# Flash.net
KiCad netlist of a schematic drawn in Altium Designer
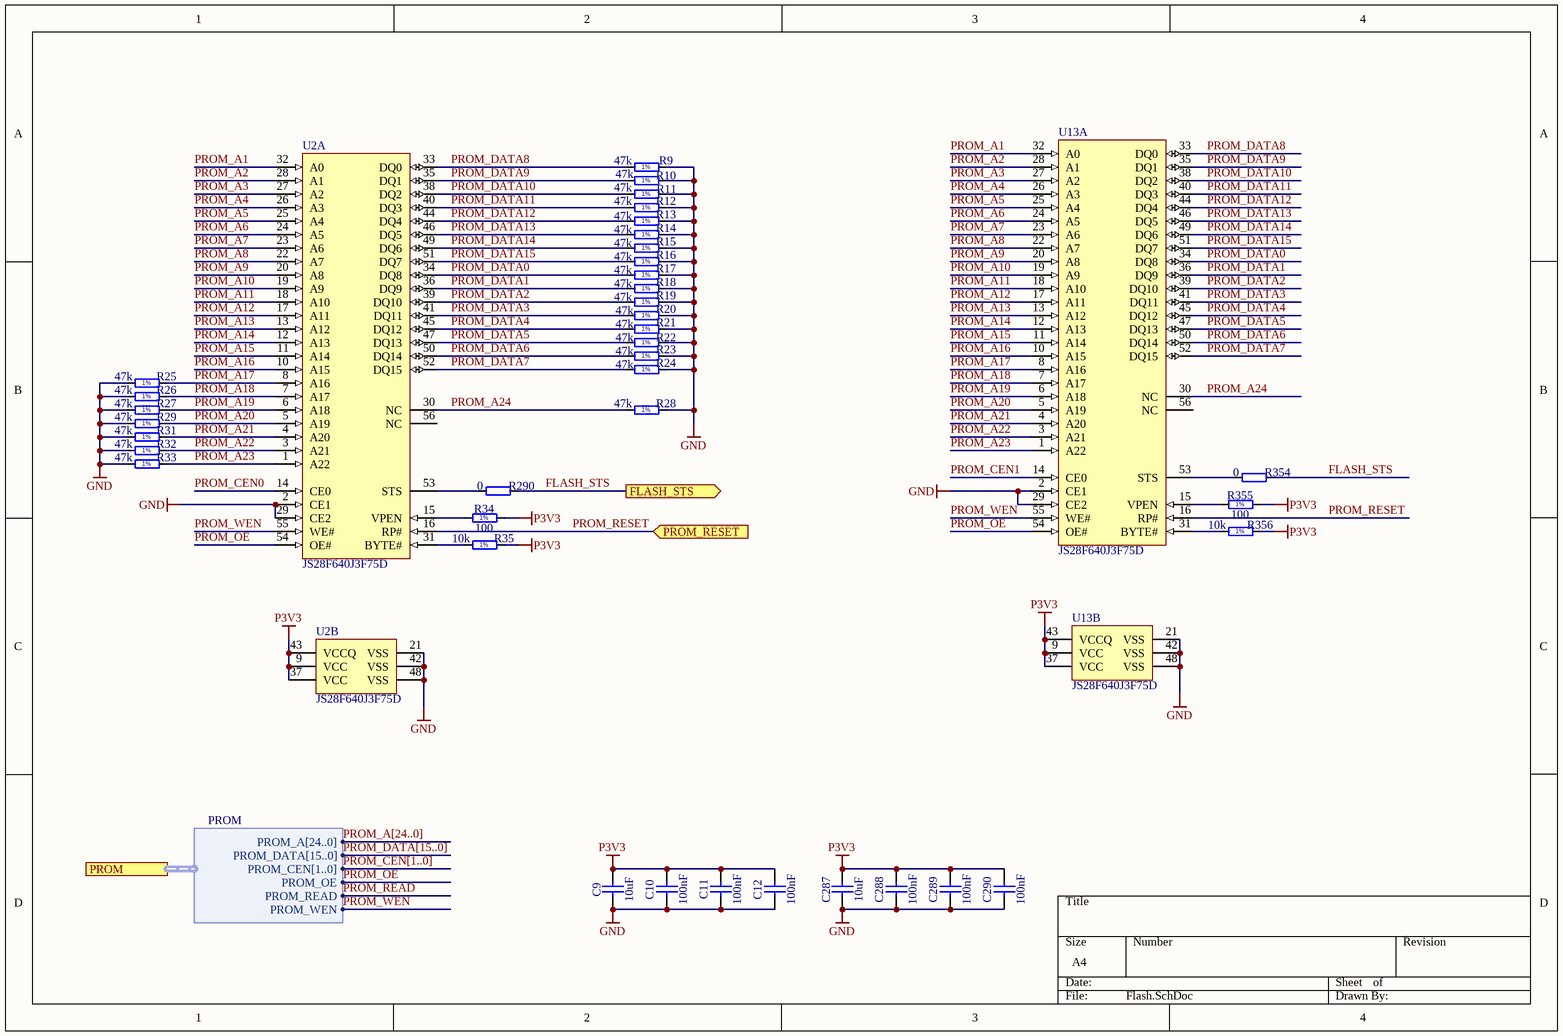
[diagram p0: Flash.SchDoc]

(export (version "E")
  (design (tool "Eeschema 10.0.6"))
  (components
    (comp (ref "C9")
      (value "10uF")
      (footprint "CAPC2012X135N")
      (description "Non-polarised capacitor")
      (fields
        (field (name "PART NUMBER") "CC0805_10UF_16V_10%_X5R")
        (field (name "VOLTAGE") "16V")
        (field (name "AUTHOR") "CERN DEM JLC")
      )
      (libsource (lib "Capacitors") (part "Capacitor - non polarized"))
    )
    (comp (ref "C10")
      (value "100nF")
      (footprint "CAPC0603X33N")
      (description "Non-polarised capacitor")
      (fields
        (field (name "MANUFACTURER") "GENERIC")
        (field (name "PART NUMBER") "CC0201_100NF_6.3V_10%_X5R")
        (field (name "AUTHOR") "CERN DEM JLC")
      )
      (libsource (lib "Capacitors") (part "Capacitor - non polarized"))
    )
    (comp (ref "C11")
      (value "100nF")
      (footprint "CAPC0603X33N")
      (description "Non-polarised capacitor")
      (fields
        (field (name "MANUFACTURER") "GENERIC")
        (field (name "PART NUMBER") "CC0201_100NF_6.3V_10%_X5R")
        (field (name "AUTHOR") "CERN DEM JLC")
      )
      (libsource (lib "Capacitors") (part "Capacitor - non polarized"))
    )
    (comp (ref "C12")
      (value "100nF")
      (footprint "CAPC0603X33N")
      (description "Non-polarised capacitor")
      (fields
        (field (name "MANUFACTURER") "GENERIC")
        (field (name "PART NUMBER") "CC0201_100NF_6.3V_10%_X5R")
        (field (name "AUTHOR") "CERN DEM JLC")
      )
      (libsource (lib "Capacitors") (part "Capacitor - non polarized"))
    )
    (comp (ref "C287")
      (value "10uF")
      (footprint "CAPC2012X135N")
      (description "Non-polarised capacitor")
      (fields
        (field (name "PART NUMBER") "CC0805_10UF_16V_10%_X5R")
        (field (name "VOLTAGE") "16V")
        (field (name "AUTHOR") "CERN DEM JLC")
      )
      (libsource (lib "Capacitors") (part "Capacitor - non polarized"))
    )
    (comp (ref "C288")
      (value "100nF")
      (footprint "CAPC0603X33N")
      (description "Non-polarised capacitor")
      (fields
        (field (name "MANUFACTURER") "GENERIC")
        (field (name "PART NUMBER") "CC0201_100NF_6.3V_10%_X5R")
        (field (name "AUTHOR") "CERN DEM JLC")
      )
      (libsource (lib "Capacitors") (part "Capacitor - non polarized"))
    )
    (comp (ref "C289")
      (value "100nF")
      (footprint "CAPC0603X33N")
      (description "Non-polarised capacitor")
      (fields
        (field (name "MANUFACTURER") "GENERIC")
        (field (name "PART NUMBER") "CC0201_100NF_6.3V_10%_X5R")
        (field (name "AUTHOR") "CERN DEM JLC")
      )
      (libsource (lib "Capacitors") (part "Capacitor - non polarized"))
    )
    (comp (ref "C290")
      (value "100nF")
      (footprint "CAPC0603X33N")
      (description "Non-polarised capacitor")
      (fields
        (field (name "MANUFACTURER") "GENERIC")
        (field (name "PART NUMBER") "CC0201_100NF_6.3V_10%_X5R")
        (field (name "AUTHOR") "CERN DEM JLC")
      )
      (libsource (lib "Capacitors") (part "Capacitor - non polarized"))
    )
    (comp (ref "R9")
      (value "47k")
      (footprint "RESC1005X40N")
      (description "Resistor - 1%")
      (fields
        (field (name "PART NUMBER") "R0402_47K_1%_0.0625W_100PPM")
        (field (name "POWER") "0.0625W")
        (field (name "AUTHOR") "CERN DEM JLC")
      )
      (libsource (lib "Resistors") (part "Resistor - 1%"))
    )
    (comp (ref "R10")
      (value "47k")
      (footprint "RESC1005X40N")
      (description "Resistor - 1%")
      (fields
        (field (name "PART NUMBER") "R0402_47K_1%_0.0625W_100PPM")
        (field (name "POWER") "0.0625W")
        (field (name "AUTHOR") "CERN DEM JLC")
      )
      (libsource (lib "Resistors") (part "Resistor - 1%"))
    )
    (comp (ref "R11")
      (value "47k")
      (footprint "RESC1005X40N")
      (description "Resistor - 1%")
      (fields
        (field (name "PART NUMBER") "R0402_47K_1%_0.0625W_100PPM")
        (field (name "POWER") "0.0625W")
        (field (name "AUTHOR") "CERN DEM JLC")
      )
      (libsource (lib "Resistors") (part "Resistor - 1%"))
    )
    (comp (ref "R12")
      (value "47k")
      (footprint "RESC1005X40N")
      (description "Resistor - 1%")
      (fields
        (field (name "PART NUMBER") "R0402_47K_1%_0.0625W_100PPM")
        (field (name "POWER") "0.0625W")
        (field (name "AUTHOR") "CERN DEM JLC")
      )
      (libsource (lib "Resistors") (part "Resistor - 1%"))
    )
    (comp (ref "R13")
      (value "47k")
      (footprint "RESC1005X40N")
      (description "Resistor - 1%")
      (fields
        (field (name "PART NUMBER") "R0402_47K_1%_0.0625W_100PPM")
        (field (name "POWER") "0.0625W")
        (field (name "AUTHOR") "CERN DEM JLC")
      )
      (libsource (lib "Resistors") (part "Resistor - 1%"))
    )
    (comp (ref "R14")
      (value "47k")
      (footprint "RESC1005X40N")
      (description "Resistor - 1%")
      (fields
        (field (name "PART NUMBER") "R0402_47K_1%_0.0625W_100PPM")
        (field (name "POWER") "0.0625W")
        (field (name "AUTHOR") "CERN DEM JLC")
      )
      (libsource (lib "Resistors") (part "Resistor - 1%"))
    )
    (comp (ref "R15")
      (value "47k")
      (footprint "RESC1005X40N")
      (description "Resistor - 1%")
      (fields
        (field (name "PART NUMBER") "R0402_47K_1%_0.0625W_100PPM")
        (field (name "POWER") "0.0625W")
        (field (name "AUTHOR") "CERN DEM JLC")
      )
      (libsource (lib "Resistors") (part "Resistor - 1%"))
    )
    (comp (ref "R16")
      (value "47k")
      (footprint "RESC1005X40N")
      (description "Resistor - 1%")
      (fields
        (field (name "PART NUMBER") "R0402_47K_1%_0.0625W_100PPM")
        (field (name "POWER") "0.0625W")
        (field (name "AUTHOR") "CERN DEM JLC")
      )
      (libsource (lib "Resistors") (part "Resistor - 1%"))
    )
    (comp (ref "R17")
      (value "47k")
      (footprint "RESC1005X40N")
      (description "Resistor - 1%")
      (fields
        (field (name "PART NUMBER") "R0402_47K_1%_0.0625W_100PPM")
        (field (name "POWER") "0.0625W")
        (field (name "AUTHOR") "CERN DEM JLC")
      )
      (libsource (lib "Resistors") (part "Resistor - 1%"))
    )
    (comp (ref "R18")
      (value "47k")
      (footprint "RESC1005X40N")
      (description "Resistor - 1%")
      (fields
        (field (name "PART NUMBER") "R0402_47K_1%_0.0625W_100PPM")
        (field (name "POWER") "0.0625W")
        (field (name "AUTHOR") "CERN DEM JLC")
      )
      (libsource (lib "Resistors") (part "Resistor - 1%"))
    )
    (comp (ref "R19")
      (value "47k")
      (footprint "RESC1005X40N")
      (description "Resistor - 1%")
      (fields
        (field (name "PART NUMBER") "R0402_47K_1%_0.0625W_100PPM")
        (field (name "POWER") "0.0625W")
        (field (name "AUTHOR") "CERN DEM JLC")
      )
      (libsource (lib "Resistors") (part "Resistor - 1%"))
    )
    (comp (ref "R20")
      (value "47k")
      (footprint "RESC1005X40N")
      (description "Resistor - 1%")
      (fields
        (field (name "PART NUMBER") "R0402_47K_1%_0.0625W_100PPM")
        (field (name "POWER") "0.0625W")
        (field (name "AUTHOR") "CERN DEM JLC")
      )
      (libsource (lib "Resistors") (part "Resistor - 1%"))
    )
    (comp (ref "R21")
      (value "47k")
      (footprint "RESC1005X40N")
      (description "Resistor - 1%")
      (fields
        (field (name "PART NUMBER") "R0402_47K_1%_0.0625W_100PPM")
        (field (name "POWER") "0.0625W")
        (field (name "AUTHOR") "CERN DEM JLC")
      )
      (libsource (lib "Resistors") (part "Resistor - 1%"))
    )
    (comp (ref "R22")
      (value "47k")
      (footprint "RESC1005X40N")
      (description "Resistor - 1%")
      (fields
        (field (name "PART NUMBER") "R0402_47K_1%_0.0625W_100PPM")
        (field (name "POWER") "0.0625W")
        (field (name "AUTHOR") "CERN DEM JLC")
      )
      (libsource (lib "Resistors") (part "Resistor - 1%"))
    )
    (comp (ref "R23")
      (value "47k")
      (footprint "RESC1005X40N")
      (description "Resistor - 1%")
      (fields
        (field (name "PART NUMBER") "R0402_47K_1%_0.0625W_100PPM")
        (field (name "POWER") "0.0625W")
        (field (name "AUTHOR") "CERN DEM JLC")
      )
      (libsource (lib "Resistors") (part "Resistor - 1%"))
    )
    (comp (ref "R24")
      (value "47k")
      (footprint "RESC1005X40N")
      (description "Resistor - 1%")
      (fields
        (field (name "PART NUMBER") "R0402_47K_1%_0.0625W_100PPM")
        (field (name "POWER") "0.0625W")
        (field (name "AUTHOR") "CERN DEM JLC")
      )
      (libsource (lib "Resistors") (part "Resistor - 1%"))
    )
    (comp (ref "R25")
      (value "47k")
      (footprint "RESC1005X40N")
      (description "Resistor - 1%")
      (fields
        (field (name "PART NUMBER") "R0402_47K_1%_0.0625W_100PPM")
        (field (name "POWER") "0.0625W")
        (field (name "AUTHOR") "CERN DEM JLC")
      )
      (libsource (lib "Resistors") (part "Resistor - 1%"))
    )
    (comp (ref "R26")
      (value "47k")
      (footprint "RESC1005X40N")
      (description "Resistor - 1%")
      (fields
        (field (name "PART NUMBER") "R0402_47K_1%_0.0625W_100PPM")
        (field (name "POWER") "0.0625W")
        (field (name "AUTHOR") "CERN DEM JLC")
      )
      (libsource (lib "Resistors") (part "Resistor - 1%"))
    )
    (comp (ref "R27")
      (value "47k")
      (footprint "RESC1005X40N")
      (description "Resistor - 1%")
      (fields
        (field (name "PART NUMBER") "R0402_47K_1%_0.0625W_100PPM")
        (field (name "POWER") "0.0625W")
        (field (name "AUTHOR") "CERN DEM JLC")
      )
      (libsource (lib "Resistors") (part "Resistor - 1%"))
    )
    (comp (ref "R28")
      (value "47k")
      (footprint "RESC1005X40N")
      (description "Resistor - 1%")
      (fields
        (field (name "PART NUMBER") "R0402_47K_1%_0.0625W_100PPM")
        (field (name "POWER") "0.0625W")
        (field (name "AUTHOR") "CERN DEM JLC")
      )
      (libsource (lib "Resistors") (part "Resistor - 1%"))
    )
    (comp (ref "R29")
      (value "47k")
      (footprint "RESC1005X40N")
      (description "Resistor - 1%")
      (fields
        (field (name "PART NUMBER") "R0402_47K_1%_0.0625W_100PPM")
        (field (name "POWER") "0.0625W")
        (field (name "AUTHOR") "CERN DEM JLC")
      )
      (libsource (lib "Resistors") (part "Resistor - 1%"))
    )
    (comp (ref "R31")
      (value "47k")
      (footprint "RESC1005X40N")
      (description "Resistor - 1%")
      (fields
        (field (name "PART NUMBER") "R0402_47K_1%_0.0625W_100PPM")
        (field (name "POWER") "0.0625W")
        (field (name "AUTHOR") "CERN DEM JLC")
      )
      (libsource (lib "Resistors") (part "Resistor - 1%"))
    )
    (comp (ref "R32")
      (value "47k")
      (footprint "RESC1005X40N")
      (description "Resistor - 1%")
      (fields
        (field (name "PART NUMBER") "R0402_47K_1%_0.0625W_100PPM")
        (field (name "POWER") "0.0625W")
        (field (name "AUTHOR") "CERN DEM JLC")
      )
      (libsource (lib "Resistors") (part "Resistor - 1%"))
    )
    (comp (ref "R33")
      (value "47k")
      (footprint "RESC1005X40N")
      (description "Resistor - 1%")
      (fields
        (field (name "PART NUMBER") "R0402_47K_1%_0.0625W_100PPM")
        (field (name "POWER") "0.0625W")
        (field (name "AUTHOR") "CERN DEM JLC")
      )
      (libsource (lib "Resistors") (part "Resistor - 1%"))
    )
    (comp (ref "R34")
      (value "100")
      (footprint "RESC1005X40N")
      (description "Resistor - 1%")
      (fields
        (field (name "PART NUMBER") "R0402_100R_1%_0.0625W_100PPM")
        (field (name "POWER") "0.0625W")
        (field (name "AUTHOR") "CERN DEM JLC")
      )
      (libsource (lib "Resistors") (part "Resistor - 1%"))
    )
    (comp (ref "R35")
      (value "10k")
      (footprint "RESC1005X40N")
      (description "Resistor - 1%")
      (fields
        (field (name "MANUFACTURER PART NUMBER") "R0402_10K_1%_0.0625W_100PPM")
        (field (name "MANUFACTURER") "GENERIC")
        (field (name "AUTHOR") "CERN DEM JLC")
      )
      (libsource (lib "Resistors") (part "Resistor - 1%"))
    )
    (comp (ref "R290")
      (value "0")
      (footprint "RESC0603X28N")
      (description "Resistor")
      (fields
        (field (name "PART NUMBER") "R0201_0R_JUMPER")
        (field (name "MANUFACTURER") "GENERIC")
        (field (name "AUTHOR") "CERN DEM JLC")
      )
      (libsource (lib "Resistors") (part "Resistor"))
    )
    (comp (ref "R354")
      (value "0")
      (footprint "RESC0603X28N")
      (description "Resistor")
      (fields
        (field (name "PART NUMBER") "R0201_0R_JUMPER")
        (field (name "MANUFACTURER") "GENERIC")
        (field (name "AUTHOR") "CERN DEM JLC")
      )
      (libsource (lib "Resistors") (part "Resistor"))
    )
    (comp (ref "R355")
      (value "100")
      (footprint "RESC1005X40N")
      (description "Resistor - 1%")
      (fields
        (field (name "PART NUMBER") "R0402_100R_1%_0.0625W_100PPM")
        (field (name "POWER") "0.0625W")
        (field (name "AUTHOR") "CERN DEM JLC")
      )
      (libsource (lib "Resistors") (part "Resistor - 1%"))
    )
    (comp (ref "R356")
      (value "10k")
      (footprint "RESC1005X40N")
      (description "Resistor - 1%")
      (fields
        (field (name "MANUFACTURER PART NUMBER") "R0402_10K_1%_0.0625W_100PPM")
        (field (name "MANUFACTURER") "GENERIC")
        (field (name "AUTHOR") "CERN DEM JLC")
      )
      (libsource (lib "Resistors") (part "Resistor - 1%"))
    )
    (comp (ref "U2")
      (value "JS28F640J3F75D")
      (footprint "MICT-JS-56_N")
      (description "64 Mb (x8/x16) Parallel NOR Flash Memory, 75 ns, 2.7 to 3.6 V, 56-pin TSOP (JS), Tape & Reel")
      (fields (field (name "VOLTAGE") "2.7V-3.6VÂ ") (field (name "MANUFACTURER") "Micron"))
      (libsource (lib "Altium Content Vault") (part "MICT-J3640JS-56"))
    )
    (comp (ref "U13")
      (value "JS28F640J3F75D")
      (footprint "MICT-JS-56_N")
      (description "64 Mb (x8/x16) Parallel NOR Flash Memory, 75 ns, 2.7 to 3.6 V, 56-pin TSOP (JS), Tape & Reel")
      (fields (field (name "VOLTAGE") "2.7V-3.6VÂ ") (field (name "MANUFACTURER") "Micron"))
      (libsource (lib "Altium Content Vault") (part "MICT-J3640JS-56"))
    )
  )
  (nets
    (net (code "3") (name "/FLASH_STS") (class "Default")
      (node (ref "R290") (pin "2") (pinfunction "2_2") (pintype "passive"))
      (node (ref "R354") (pin "2") (pinfunction "2_2") (pintype "passive"))
    )
    (net (code "4") (name "/PROM_A1") (class "Default")
      (node (ref "U13") (pin "32") (pinfunction "A0_32") (pintype "input"))
      (node (ref "U2") (pin "32") (pinfunction "A0_32") (pintype "input"))
    )
    (net (code "5") (name "/PROM_A2") (class "Default")
      (node (ref "U13") (pin "28") (pinfunction "A1_28") (pintype "input"))
      (node (ref "U2") (pin "28") (pinfunction "A1_28") (pintype "input"))
    )
    (net (code "6") (name "/PROM_A3") (class "Default")
      (node (ref "U13") (pin "27") (pinfunction "A2_27") (pintype "input"))
      (node (ref "U2") (pin "27") (pinfunction "A2_27") (pintype "input"))
    )
    (net (code "7") (name "/PROM_A4") (class "Default")
      (node (ref "U13") (pin "26") (pinfunction "A3_26") (pintype "input"))
      (node (ref "U2") (pin "26") (pinfunction "A3_26") (pintype "input"))
    )
    (net (code "8") (name "/PROM_A5") (class "Default")
      (node (ref "U13") (pin "25") (pinfunction "A4_25") (pintype "input"))
      (node (ref "U2") (pin "25") (pinfunction "A4_25") (pintype "input"))
    )
    (net (code "9") (name "/PROM_A6") (class "Default")
      (node (ref "U13") (pin "24") (pinfunction "A5_24") (pintype "input"))
      (node (ref "U2") (pin "24") (pinfunction "A5_24") (pintype "input"))
    )
    (net (code "10") (name "/PROM_A7") (class "Default")
      (node (ref "U13") (pin "23") (pinfunction "A6_23") (pintype "input"))
      (node (ref "U2") (pin "23") (pinfunction "A6_23") (pintype "input"))
    )
    (net (code "11") (name "/PROM_A8") (class "Default")
      (node (ref "U13") (pin "22") (pinfunction "A7_22") (pintype "input"))
      (node (ref "U2") (pin "22") (pinfunction "A7_22") (pintype "input"))
    )
    (net (code "12") (name "/PROM_A9") (class "Default")
      (node (ref "U13") (pin "20") (pinfunction "A8_20") (pintype "input"))
      (node (ref "U2") (pin "20") (pinfunction "A8_20") (pintype "input"))
    )
    (net (code "13") (name "/PROM_A10") (class "Default")
      (node (ref "U13") (pin "19") (pinfunction "A9_19") (pintype "input"))
      (node (ref "U2") (pin "19") (pinfunction "A9_19") (pintype "input"))
    )
    (net (code "14") (name "/PROM_A11") (class "Default")
      (node (ref "U13") (pin "18") (pinfunction "A10_18") (pintype "input"))
      (node (ref "U2") (pin "18") (pinfunction "A10_18") (pintype "input"))
    )
    (net (code "15") (name "/PROM_A12") (class "Default")
      (node (ref "U13") (pin "17") (pinfunction "A11_17") (pintype "input"))
      (node (ref "U2") (pin "17") (pinfunction "A11_17") (pintype "input"))
    )
    (net (code "16") (name "/PROM_A13") (class "Default")
      (node (ref "U13") (pin "13") (pinfunction "A12_13") (pintype "input"))
      (node (ref "U2") (pin "13") (pinfunction "A12_13") (pintype "input"))
    )
    (net (code "17") (name "/PROM_A14") (class "Default")
      (node (ref "U13") (pin "12") (pinfunction "A13_12") (pintype "input"))
      (node (ref "U2") (pin "12") (pinfunction "A13_12") (pintype "input"))
    )
    (net (code "18") (name "/PROM_A15") (class "Default")
      (node (ref "U13") (pin "11") (pinfunction "A14_11") (pintype "input"))
      (node (ref "U2") (pin "11") (pinfunction "A14_11") (pintype "input"))
    )
    (net (code "19") (name "/PROM_A16") (class "Default")
      (node (ref "U13") (pin "10") (pinfunction "A15_10") (pintype "input"))
      (node (ref "U2") (pin "10") (pinfunction "A15_10") (pintype "input"))
    )
    (net (code "20") (name "/PROM_A17") (class "Default")
      (node (ref "R25") (pin "2") (pinfunction "2_2") (pintype "passive"))
      (node (ref "U13") (pin "8") (pinfunction "A16_8") (pintype "input"))
      (node (ref "U2") (pin "8") (pinfunction "A16_8") (pintype "input"))
    )
    (net (code "21") (name "/PROM_A18") (class "Default")
      (node (ref "R26") (pin "2") (pinfunction "2_2") (pintype "passive"))
      (node (ref "U13") (pin "7") (pinfunction "A17_7") (pintype "input"))
      (node (ref "U2") (pin "7") (pinfunction "A17_7") (pintype "input"))
    )
    (net (code "22") (name "/PROM_A19") (class "Default")
      (node (ref "R27") (pin "2") (pinfunction "2_2") (pintype "passive"))
      (node (ref "U13") (pin "6") (pinfunction "A18_6") (pintype "input"))
      (node (ref "U2") (pin "6") (pinfunction "A18_6") (pintype "input"))
    )
    (net (code "23") (name "/PROM_A20") (class "Default")
      (node (ref "R29") (pin "2") (pinfunction "2_2") (pintype "passive"))
      (node (ref "U13") (pin "5") (pinfunction "A19_5") (pintype "input"))
      (node (ref "U2") (pin "5") (pinfunction "A19_5") (pintype "input"))
    )
    (net (code "24") (name "/PROM_A21") (class "Default")
      (node (ref "R31") (pin "2") (pinfunction "2_2") (pintype "passive"))
      (node (ref "U13") (pin "4") (pinfunction "A20_4") (pintype "input"))
      (node (ref "U2") (pin "4") (pinfunction "A20_4") (pintype "input"))
    )
    (net (code "25") (name "/PROM_A22") (class "Default")
      (node (ref "R32") (pin "2") (pinfunction "2_2") (pintype "passive"))
      (node (ref "U13") (pin "3") (pinfunction "A21_3") (pintype "input"))
      (node (ref "U2") (pin "3") (pinfunction "A21_3") (pintype "input"))
    )
    (net (code "26") (name "/PROM_A23") (class "Default")
      (node (ref "R33") (pin "2") (pinfunction "2_2") (pintype "passive"))
      (node (ref "U13") (pin "1") (pinfunction "A22_1") (pintype "input"))
      (node (ref "U2") (pin "1") (pinfunction "A22_1") (pintype "input"))
    )
    (net (code "27") (name "/PROM_A24") (class "Default")
      (node (ref "R28") (pin "1") (pinfunction "1_1") (pintype "passive"))
      (node (ref "U13") (pin "30") (pinfunction "NC_30") (pintype "passive"))
      (node (ref "U2") (pin "30") (pinfunction "NC_30") (pintype "passive"))
    )
    (net (code "29") (name "/PROM_CEN0") (class "Default")
      (node (ref "U2") (pin "14") (pinfunction "CE0_14") (pintype "input"))
    )
    (net (code "30") (name "/PROM_CEN1") (class "Default")
      (node (ref "U13") (pin "14") (pinfunction "CE0_14") (pintype "input"))
    )
    (net (code "31") (name "/PROM_DATA0") (class "Default")
      (node (ref "R17") (pin "1") (pinfunction "1_1") (pintype "passive"))
      (node (ref "U13") (pin "34") (pinfunction "DQ8_34") (pintype "bidirectional"))
      (node (ref "U2") (pin "34") (pinfunction "DQ8_34") (pintype "bidirectional"))
    )
    (net (code "32") (name "/PROM_DATA1") (class "Default")
      (node (ref "R18") (pin "1") (pinfunction "1_1") (pintype "passive"))
      (node (ref "U13") (pin "36") (pinfunction "DQ9_36") (pintype "bidirectional"))
      (node (ref "U2") (pin "36") (pinfunction "DQ9_36") (pintype "bidirectional"))
    )
    (net (code "33") (name "/PROM_DATA2") (class "Default")
      (node (ref "R19") (pin "1") (pinfunction "1_1") (pintype "passive"))
      (node (ref "U13") (pin "39") (pinfunction "DQ10_39") (pintype "bidirectional"))
      (node (ref "U2") (pin "39") (pinfunction "DQ10_39") (pintype "bidirectional"))
    )
    (net (code "34") (name "/PROM_DATA3") (class "Default")
      (node (ref "R20") (pin "1") (pinfunction "1_1") (pintype "passive"))
      (node (ref "U13") (pin "41") (pinfunction "DQ11_41") (pintype "bidirectional"))
      (node (ref "U2") (pin "41") (pinfunction "DQ11_41") (pintype "bidirectional"))
    )
    (net (code "35") (name "/PROM_DATA4") (class "Default")
      (node (ref "R21") (pin "1") (pinfunction "1_1") (pintype "passive"))
      (node (ref "U13") (pin "45") (pinfunction "DQ12_45") (pintype "bidirectional"))
      (node (ref "U2") (pin "45") (pinfunction "DQ12_45") (pintype "bidirectional"))
    )
    (net (code "36") (name "/PROM_DATA5") (class "Default")
      (node (ref "R22") (pin "1") (pinfunction "1_1") (pintype "passive"))
      (node (ref "U13") (pin "47") (pinfunction "DQ13_47") (pintype "bidirectional"))
      (node (ref "U2") (pin "47") (pinfunction "DQ13_47") (pintype "bidirectional"))
    )
    (net (code "37") (name "/PROM_DATA6") (class "Default")
      (node (ref "R23") (pin "1") (pinfunction "1_1") (pintype "passive"))
      (node (ref "U13") (pin "50") (pinfunction "DQ14_50") (pintype "bidirectional"))
      (node (ref "U2") (pin "50") (pinfunction "DQ14_50") (pintype "bidirectional"))
    )
    (net (code "38") (name "/PROM_DATA7") (class "Default")
      (node (ref "R24") (pin "1") (pinfunction "1_1") (pintype "passive"))
      (node (ref "U13") (pin "52") (pinfunction "DQ15_52") (pintype "bidirectional"))
      (node (ref "U2") (pin "52") (pinfunction "DQ15_52") (pintype "bidirectional"))
    )
    (net (code "39") (name "/PROM_DATA8") (class "Default")
      (node (ref "R9") (pin "1") (pinfunction "1_1") (pintype "passive"))
      (node (ref "U13") (pin "33") (pinfunction "DQ0_33") (pintype "bidirectional"))
      (node (ref "U2") (pin "33") (pinfunction "DQ0_33") (pintype "bidirectional"))
    )
    (net (code "40") (name "/PROM_DATA9") (class "Default")
      (node (ref "R10") (pin "1") (pinfunction "1_1") (pintype "passive"))
      (node (ref "U13") (pin "35") (pinfunction "DQ1_35") (pintype "bidirectional"))
      (node (ref "U2") (pin "35") (pinfunction "DQ1_35") (pintype "bidirectional"))
    )
    (net (code "41") (name "/PROM_DATA10") (class "Default")
      (node (ref "R11") (pin "1") (pinfunction "1_1") (pintype "passive"))
      (node (ref "U13") (pin "38") (pinfunction "DQ2_38") (pintype "bidirectional"))
      (node (ref "U2") (pin "38") (pinfunction "DQ2_38") (pintype "bidirectional"))
    )
    (net (code "42") (name "/PROM_DATA11") (class "Default")
      (node (ref "R12") (pin "1") (pinfunction "1_1") (pintype "passive"))
      (node (ref "U13") (pin "40") (pinfunction "DQ3_40") (pintype "bidirectional"))
      (node (ref "U2") (pin "40") (pinfunction "DQ3_40") (pintype "bidirectional"))
    )
    (net (code "43") (name "/PROM_DATA12") (class "Default")
      (node (ref "R13") (pin "1") (pinfunction "1_1") (pintype "passive"))
      (node (ref "U13") (pin "44") (pinfunction "DQ4_44") (pintype "bidirectional"))
      (node (ref "U2") (pin "44") (pinfunction "DQ4_44") (pintype "bidirectional"))
    )
    (net (code "44") (name "/PROM_DATA13") (class "Default")
      (node (ref "R14") (pin "1") (pinfunction "1_1") (pintype "passive"))
      (node (ref "U13") (pin "46") (pinfunction "DQ5_46") (pintype "bidirectional"))
      (node (ref "U2") (pin "46") (pinfunction "DQ5_46") (pintype "bidirectional"))
    )
    (net (code "45") (name "/PROM_DATA14") (class "Default")
      (node (ref "R15") (pin "1") (pinfunction "1_1") (pintype "passive"))
      (node (ref "U13") (pin "49") (pinfunction "DQ6_49") (pintype "bidirectional"))
      (node (ref "U2") (pin "49") (pinfunction "DQ6_49") (pintype "bidirectional"))
    )
    (net (code "46") (name "/PROM_DATA15") (class "Default")
      (node (ref "R16") (pin "1") (pinfunction "1_1") (pintype "passive"))
      (node (ref "U13") (pin "51") (pinfunction "DQ7_51") (pintype "bidirectional"))
      (node (ref "U2") (pin "51") (pinfunction "DQ7_51") (pintype "bidirectional"))
    )
    (net (code "48") (name "/PROM_OE") (class "Default")
      (node (ref "U13") (pin "54") (pinfunction "OE#_54") (pintype "input"))
      (node (ref "U2") (pin "54") (pinfunction "OE#_54") (pintype "input"))
    )
    (net (code "49") (name "/PROM_RESET") (class "Default")
      (node (ref "U13") (pin "16") (pinfunction "RP#_16") (pintype "input"))
      (node (ref "U2") (pin "16") (pinfunction "RP#_16") (pintype "input"))
    )
    (net (code "50") (name "/PROM_WEN") (class "Default")
      (node (ref "U13") (pin "55") (pinfunction "WE#_55") (pintype "input"))
      (node (ref "U2") (pin "55") (pinfunction "WE#_55") (pintype "input"))
    )
    (net (code "53") (name "GND") (class "Default")
      (node (ref "C10") (pin "2") (pinfunction "2_2") (pintype "passive"))
      (node (ref "C11") (pin "2") (pinfunction "2_2") (pintype "passive"))
      (node (ref "C12") (pin "2") (pinfunction "2_2") (pintype "passive"))
      (node (ref "C287") (pin "1") (pinfunction "1_1") (pintype "passive"))
      (node (ref "C288") (pin "2") (pinfunction "2_2") (pintype "passive"))
      (node (ref "C289") (pin "2") (pinfunction "2_2") (pintype "passive"))
      (node (ref "C290") (pin "2") (pinfunction "2_2") (pintype "passive"))
      (node (ref "C9") (pin "1") (pinfunction "1_1") (pintype "passive"))
      (node (ref "R10") (pin "2") (pinfunction "2_2") (pintype "passive"))
      (node (ref "R11") (pin "2") (pinfunction "2_2") (pintype "passive"))
      (node (ref "R12") (pin "2") (pinfunction "2_2") (pintype "passive"))
      (node (ref "R13") (pin "2") (pinfunction "2_2") (pintype "passive"))
      (node (ref "R14") (pin "2") (pinfunction "2_2") (pintype "passive"))
      (node (ref "R15") (pin "2") (pinfunction "2_2") (pintype "passive"))
      (node (ref "R16") (pin "2") (pinfunction "2_2") (pintype "passive"))
      (node (ref "R17") (pin "2") (pinfunction "2_2") (pintype "passive"))
      (node (ref "R18") (pin "2") (pinfunction "2_2") (pintype "passive"))
      (node (ref "R19") (pin "2") (pinfunction "2_2") (pintype "passive"))
      (node (ref "R20") (pin "2") (pinfunction "2_2") (pintype "passive"))
      (node (ref "R21") (pin "2") (pinfunction "2_2") (pintype "passive"))
      (node (ref "R22") (pin "2") (pinfunction "2_2") (pintype "passive"))
      (node (ref "R23") (pin "2") (pinfunction "2_2") (pintype "passive"))
      (node (ref "R24") (pin "2") (pinfunction "2_2") (pintype "passive"))
      (node (ref "R25") (pin "1") (pinfunction "1_1") (pintype "passive"))
      (node (ref "R26") (pin "1") (pinfunction "1_1") (pintype "passive"))
      (node (ref "R27") (pin "1") (pinfunction "1_1") (pintype "passive"))
      (node (ref "R28") (pin "2") (pinfunction "2_2") (pintype "passive"))
      (node (ref "R29") (pin "1") (pinfunction "1_1") (pintype "passive"))
      (node (ref "R31") (pin "1") (pinfunction "1_1") (pintype "passive"))
      (node (ref "R32") (pin "1") (pinfunction "1_1") (pintype "passive"))
      (node (ref "R33") (pin "1") (pinfunction "1_1") (pintype "passive"))
      (node (ref "R9") (pin "2") (pinfunction "2_2") (pintype "passive"))
      (node (ref "U13") (pin "2") (pinfunction "CE1_2") (pintype "input"))
      (node (ref "U13") (pin "21") (pinfunction "VSS_21") (pintype "power_in"))
      (node (ref "U13") (pin "29") (pinfunction "CE2_29") (pintype "input"))
      (node (ref "U13") (pin "42") (pinfunction "VSS_42") (pintype "power_in"))
      (node (ref "U13") (pin "48") (pinfunction "VSS_48") (pintype "power_in"))
      (node (ref "U2") (pin "2") (pinfunction "CE1_2") (pintype "input"))
      (node (ref "U2") (pin "21") (pinfunction "VSS_21") (pintype "power_in"))
      (node (ref "U2") (pin "29") (pinfunction "CE2_29") (pintype "input"))
      (node (ref "U2") (pin "42") (pinfunction "VSS_42") (pintype "power_in"))
      (node (ref "U2") (pin "48") (pinfunction "VSS_48") (pintype "power_in"))
    )
    (net (code "54") (name "Net-(U2A-BYTE#)") (class "Default")
      (node (ref "R35") (pin "1") (pinfunction "1_1") (pintype "passive"))
      (node (ref "U2") (pin "31") (pinfunction "BYTE#_31") (pintype "input"))
    )
    (net (code "55") (name "Net-(U2A-STS)") (class "Default")
      (node (ref "R290") (pin "1") (pinfunction "1_1") (pintype "passive"))
      (node (ref "U2") (pin "53") (pinfunction "STS_53") (pintype "tri_state"))
    )
    (net (code "56") (name "Net-(U2A-VPEN)") (class "Default")
      (node (ref "R34") (pin "1") (pinfunction "1_1") (pintype "passive"))
      (node (ref "U2") (pin "15") (pinfunction "VPEN_15") (pintype "input"))
    )
    (net (code "57") (name "Net-(U13A-BYTE#)") (class "Default")
      (node (ref "R356") (pin "1") (pinfunction "1_1") (pintype "passive"))
      (node (ref "U13") (pin "31") (pinfunction "BYTE#_31") (pintype "input"))
    )
    (net (code "58") (name "Net-(U13A-STS)") (class "Default")
      (node (ref "R354") (pin "1") (pinfunction "1_1") (pintype "passive"))
      (node (ref "U13") (pin "53") (pinfunction "STS_53") (pintype "tri_state"))
    )
    (net (code "59") (name "Net-(U13A-VPEN)") (class "Default")
      (node (ref "R355") (pin "1") (pinfunction "1_1") (pintype "passive"))
      (node (ref "U13") (pin "15") (pinfunction "VPEN_15") (pintype "input"))
    )
    (net (code "60") (name "P3V3") (class "Default")
      (node (ref "C10") (pin "1") (pinfunction "1_1") (pintype "passive"))
      (node (ref "C11") (pin "1") (pinfunction "1_1") (pintype "passive"))
      (node (ref "C12") (pin "1") (pinfunction "1_1") (pintype "passive"))
      (node (ref "C287") (pin "2") (pinfunction "2_2") (pintype "passive"))
      (node (ref "C288") (pin "1") (pinfunction "1_1") (pintype "passive"))
      (node (ref "C289") (pin "1") (pinfunction "1_1") (pintype "passive"))
      (node (ref "C290") (pin "1") (pinfunction "1_1") (pintype "passive"))
      (node (ref "C9") (pin "2") (pinfunction "2_2") (pintype "passive"))
      (node (ref "R34") (pin "2") (pinfunction "2_2") (pintype "passive"))
      (node (ref "R35") (pin "2") (pinfunction "2_2") (pintype "passive"))
      (node (ref "R355") (pin "2") (pinfunction "2_2") (pintype "passive"))
      (node (ref "R356") (pin "2") (pinfunction "2_2") (pintype "passive"))
      (node (ref "U13") (pin "37") (pinfunction "VCC_37") (pintype "power_in"))
      (node (ref "U13") (pin "43") (pinfunction "VCCQ_43") (pintype "power_in"))
      (node (ref "U13") (pin "9") (pinfunction "VCC_9") (pintype "power_in"))
      (node (ref "U2") (pin "37") (pinfunction "VCC_37") (pintype "power_in"))
      (node (ref "U2") (pin "43") (pinfunction "VCCQ_43") (pintype "power_in"))
      (node (ref "U2") (pin "9") (pinfunction "VCC_9") (pintype "power_in"))
    )
    (net (code "61") (name "unconnected-(U2A-NC-Pad56)") (class "Default")
      (node (ref "U2") (pin "56") (pinfunction "NC_56") (pintype "passive"))
    )
    (net (code "62") (name "unconnected-(U13A-NC-Pad56)") (class "Default")
      (node (ref "U13") (pin "56") (pinfunction "NC_56") (pintype "passive"))
    )
  )
)
